# VESC_KS75600_comm.net
KiCad netlist of a schematic drawn in Altium Designer
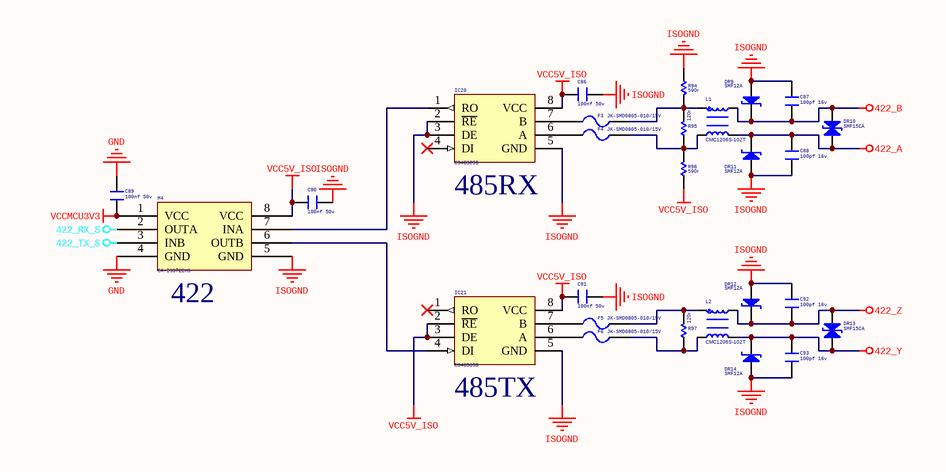
[diagram p0: VESC_KS75600_comm.SchDoc]

(export (version "E")
  (design (tool "Eeschema 10.0.6"))
  (components
    (comp (ref "C86")
      (value "100nf 50v")
      (footprint "C 0603")
      (description "无极性贴片电容")
      (fields (field (name "VOLTAGE") "50v"))
      (libsource (lib "电阻-电容-电感") (part "C"))
    )
    (comp (ref "C87")
      (value "100pf 16v")
      (footprint "C 0603")
      (description "无极性贴片电容")
      (fields (field (name "VOLTAGE") "16v"))
      (libsource (lib "电阻-电容-电感") (part "C"))
    )
    (comp (ref "C88")
      (value "100pf 16v")
      (footprint "C 0603")
      (description "无极性贴片电容")
      (fields (field (name "VOLTAGE") "16v"))
      (libsource (lib "电阻-电容-电感") (part "C"))
    )
    (comp (ref "C89")
      (value "100nf 50v")
      (footprint "C 0603")
      (description "无极性贴片电容")
      (fields (field (name "VOLTAGE") "50v"))
      (libsource (lib "电阻-电容-电感") (part "C"))
    )
    (comp (ref "C90")
      (value "100nf 50v")
      (footprint "C 0603")
      (description "无极性贴片电容")
      (fields (field (name "VOLTAGE") "50v"))
      (libsource (lib "电阻-电容-电感") (part "C"))
    )
    (comp (ref "C91")
      (value "100nf 50v")
      (footprint "C 0603")
      (description "无极性贴片电容")
      (fields (field (name "VOLTAGE") "50v"))
      (libsource (lib "电阻-电容-电感") (part "C"))
    )
    (comp (ref "C92")
      (value "100pf 16v")
      (footprint "C 0603")
      (description "无极性贴片电容")
      (fields (field (name "VOLTAGE") "16v"))
      (libsource (lib "电阻-电容-电感") (part "C"))
    )
    (comp (ref "C93")
      (value "100pf 16v")
      (footprint "C 0603")
      (description "无极性贴片电容")
      (fields (field (name "VOLTAGE") "16v"))
      (libsource (lib "电阻-电容-电感") (part "C"))
    )
    (comp (ref "DR9")
      (value "SMF12A")
      (footprint "SOD-123F")
      (description "瞬态电压抑制二极管(单向)")
      (libsource (lib "二极管-整流桥") (part "DR_S"))
    )
    (comp (ref "DR10")
      (value "SMF15CA")
      (footprint "SOD-123F")
      (description "瞬态电压抑制二极管")
      (libsource (lib "二极管-整流桥") (part "DR"))
    )
    (comp (ref "DR11")
      (value "SMF12A")
      (footprint "SOD-123F")
      (description "瞬态电压抑制二极管(单向)")
      (libsource (lib "二极管-整流桥") (part "DR_S"))
    )
    (comp (ref "DR12")
      (value "SMF12A")
      (footprint "SOD-123F")
      (description "瞬态电压抑制二极管(单向)")
      (libsource (lib "二极管-整流桥") (part "DR_S"))
    )
    (comp (ref "DR13")
      (value "SMF15CA")
      (footprint "SOD-123F")
      (description "瞬态电压抑制二极管")
      (libsource (lib "二极管-整流桥") (part "DR"))
    )
    (comp (ref "DR14")
      (value "SMF12A")
      (footprint "SOD-123F")
      (description "瞬态电压抑制二极管(单向)")
      (libsource (lib "二极管-整流桥") (part "DR_S"))
    )
    (comp (ref "F3")
      (value "JK-SMD0805-010/15V")
      (footprint "FU 0805")
      (description "贴片保险丝")
      (libsource (lib "保险丝-晶振") (part "FU"))
    )
    (comp (ref "F4")
      (value "JK-SMD0805-010/15V")
      (footprint "FU 0805")
      (description "贴片保险丝")
      (libsource (lib "保险丝-晶振") (part "FU"))
    )
    (comp (ref "F5")
      (value "JK-SMD0805-010/15V")
      (footprint "FU 0805")
      (description "贴片保险丝")
      (libsource (lib "保险丝-晶振") (part "FU"))
    )
    (comp (ref "F6")
      (value "JK-SMD0805-010/15V")
      (footprint "FU 0805")
      (description "贴片保险丝")
      (libsource (lib "保险丝-晶振") (part "FU"))
    )
    (comp (ref "IC20")
      (value "CS48505S")
      (footprint "SOP8_N")
      (description "RS485总线收发芯片")
      (libsource (lib "IC芯片") (part "SP3485"))
    )
    (comp (ref "IC21")
      (value "CS48505S")
      (footprint "SOP8_N")
      (description "RS485总线收发芯片")
      (libsource (lib "IC芯片") (part "SP3485"))
    )
    (comp (ref "L1")
      (value "CMC1206S-102T")
      (footprint "D_C_C_1206")
      (description "共模电感")
      (libsource (lib "电阻-电容-电感") (part "L-CMC"))
    )
    (comp (ref "L2")
      (value "CMC1206S-102T")
      (footprint "D_C_C_1206")
      (description "共模电感")
      (libsource (lib "电阻-电容-电感") (part "L-CMC"))
    )
    (comp (ref "M4")
      (value "CA-IS3722HS")
      (footprint "SOP8_N")
      (description "正反向数字隔离器")
      (libsource (lib "IC芯片") (part "CA-IS3722"))
    )
    (comp (ref "R94")
      (value "590r")
      (footprint "R 0603")
      (description "贴片电阻")
      (libsource (lib "电阻-电容-电感") (part "R"))
    )
    (comp (ref "R95")
      (value "120r")
      (footprint "R 0603")
      (description "贴片电阻")
      (libsource (lib "电阻-电容-电感") (part "R"))
    )
    (comp (ref "R96")
      (value "590r")
      (footprint "R 0603")
      (description "贴片电阻")
      (libsource (lib "电阻-电容-电感") (part "R"))
    )
    (comp (ref "R97")
      (value "120r")
      (footprint "R 0603")
      (description "贴片电阻")
      (libsource (lib "电阻-电容-电感") (part "R"))
    )
  )
  (nets
    (net (code "1") (name "422_A") (class "Default")
      (node (ref "C88") (pin "2") (pinfunction "2_2") (pintype "passive"))
      (node (ref "DR10") (pin "2") (pinfunction "K_2") (pintype "passive"))
      (node (ref "DR11") (pin "2") (pinfunction "K_2") (pintype "passive"))
      (node (ref "L1") (pin "3") (pinfunction "3_3") (pintype "passive"))
    )
    (net (code "2") (name "422_B") (class "Default")
      (node (ref "C87") (pin "2") (pinfunction "2_2") (pintype "passive"))
      (node (ref "DR10") (pin "1") (pinfunction "A_1") (pintype "passive"))
      (node (ref "DR9") (pin "2") (pinfunction "K_2") (pintype "passive"))
      (node (ref "L1") (pin "2") (pinfunction "2_2") (pintype "passive"))
    )
    (net (code "3") (name "422_RX_S") (class "Default")
      (node (ref "M4") (pin "2") (pinfunction "OUTA_2") (pintype "passive"))
    )
    (net (code "4") (name "422_TX_S") (class "Default")
      (node (ref "M4") (pin "3") (pinfunction "INB_3") (pintype "passive"))
    )
    (net (code "5") (name "422_Y") (class "Default")
      (node (ref "C93") (pin "2") (pinfunction "2_2") (pintype "passive"))
      (node (ref "DR13") (pin "2") (pinfunction "K_2") (pintype "passive"))
      (node (ref "DR14") (pin "2") (pinfunction "K_2") (pintype "passive"))
      (node (ref "L2") (pin "3") (pinfunction "3_3") (pintype "passive"))
    )
    (net (code "6") (name "422_Z") (class "Default")
      (node (ref "C92") (pin "2") (pinfunction "2_2") (pintype "passive"))
      (node (ref "DR12") (pin "2") (pinfunction "K_2") (pintype "passive"))
      (node (ref "DR13") (pin "1") (pinfunction "A_1") (pintype "passive"))
      (node (ref "L2") (pin "2") (pinfunction "2_2") (pintype "passive"))
    )
    (net (code "7") (name "GND") (class "Default")
      (node (ref "C89") (pin "1") (pinfunction "1_1") (pintype "passive"))
      (node (ref "M4") (pin "4") (pinfunction "GND_4") (pintype "passive"))
    )
    (net (code "8") (name "ISOGND") (class "Default")
      (node (ref "C86") (pin "2") (pinfunction "2_2") (pintype "passive"))
      (node (ref "C87") (pin "1") (pinfunction "1_1") (pintype "passive"))
      (node (ref "C88") (pin "1") (pinfunction "1_1") (pintype "passive"))
      (node (ref "C90") (pin "2") (pinfunction "2_2") (pintype "passive"))
      (node (ref "C91") (pin "2") (pinfunction "2_2") (pintype "passive"))
      (node (ref "C92") (pin "1") (pinfunction "1_1") (pintype "passive"))
      (node (ref "C93") (pin "1") (pinfunction "1_1") (pintype "passive"))
      (node (ref "DR11") (pin "1") (pinfunction "A_1") (pintype "passive"))
      (node (ref "DR12") (pin "1") (pinfunction "A_1") (pintype "passive"))
      (node (ref "DR14") (pin "1") (pinfunction "A_1") (pintype "passive"))
      (node (ref "DR9") (pin "1") (pinfunction "A_1") (pintype "passive"))
      (node (ref "IC20") (pin "2") (pinfunction "~{RE}_2") (pintype "passive"))
      (node (ref "IC20") (pin "3") (pinfunction "DE_3") (pintype "passive"))
      (node (ref "IC20") (pin "5") (pinfunction "GND_5") (pintype "passive"))
      (node (ref "IC21") (pin "5") (pinfunction "GND_5") (pintype "passive"))
      (node (ref "M4") (pin "5") (pinfunction "GND_5") (pintype "passive"))
      (node (ref "R94") (pin "1") (pinfunction "1_1") (pintype "passive"))
    )
    (net (code "9") (name "Net-(F3-Pad2)") (class "Default")
      (node (ref "F3") (pin "2") (pinfunction "2_2") (pintype "passive"))
      (node (ref "L1") (pin "1") (pinfunction "1_1") (pintype "passive"))
      (node (ref "R94") (pin "2") (pinfunction "2_2") (pintype "passive"))
      (node (ref "R95") (pin "2") (pinfunction "2_2") (pintype "passive"))
    )
    (net (code "10") (name "Net-(F4-Pad2)") (class "Default")
      (node (ref "F4") (pin "2") (pinfunction "2_2") (pintype "passive"))
      (node (ref "L1") (pin "4") (pinfunction "4_4") (pintype "passive"))
      (node (ref "R95") (pin "1") (pinfunction "1_1") (pintype "passive"))
      (node (ref "R96") (pin "2") (pinfunction "2_2") (pintype "passive"))
    )
    (net (code "11") (name "Net-(F5-Pad2)") (class "Default")
      (node (ref "F5") (pin "2") (pinfunction "2_2") (pintype "passive"))
      (node (ref "L2") (pin "1") (pinfunction "1_1") (pintype "passive"))
      (node (ref "R97") (pin "2") (pinfunction "2_2") (pintype "passive"))
    )
    (net (code "12") (name "Net-(F6-Pad2)") (class "Default")
      (node (ref "F6") (pin "2") (pinfunction "2_2") (pintype "passive"))
      (node (ref "L2") (pin "4") (pinfunction "4_4") (pintype "passive"))
      (node (ref "R97") (pin "1") (pinfunction "1_1") (pintype "passive"))
    )
    (net (code "13") (name "Net-(IC20-A)") (class "Default")
      (node (ref "F4") (pin "1") (pinfunction "1_1") (pintype "passive"))
      (node (ref "IC20") (pin "6") (pinfunction "A_6") (pintype "passive"))
    )
    (net (code "14") (name "Net-(IC20-B)") (class "Default")
      (node (ref "F3") (pin "1") (pinfunction "1_1") (pintype "passive"))
      (node (ref "IC20") (pin "7") (pinfunction "B_7") (pintype "passive"))
    )
    (net (code "15") (name "Net-(IC20-RO)") (class "Default")
      (node (ref "IC20") (pin "1") (pinfunction "RO_1") (pintype "output"))
      (node (ref "M4") (pin "7") (pinfunction "INA_7") (pintype "passive"))
    )
    (net (code "16") (name "Net-(IC21-A)") (class "Default")
      (node (ref "F6") (pin "1") (pinfunction "1_1") (pintype "passive"))
      (node (ref "IC21") (pin "6") (pinfunction "A_6") (pintype "passive"))
    )
    (net (code "17") (name "Net-(IC21-B)") (class "Default")
      (node (ref "F5") (pin "1") (pinfunction "1_1") (pintype "passive"))
      (node (ref "IC21") (pin "7") (pinfunction "B_7") (pintype "passive"))
    )
    (net (code "18") (name "Net-(IC21-DI)") (class "Default")
      (node (ref "IC21") (pin "4") (pinfunction "DI_4") (pintype "input"))
      (node (ref "M4") (pin "6") (pinfunction "OUTB_6") (pintype "passive"))
    )
    (net (code "19") (name "VCC5V_ISO") (class "Default")
      (node (ref "C86") (pin "1") (pinfunction "1_1") (pintype "passive"))
      (node (ref "C90") (pin "1") (pinfunction "1_1") (pintype "passive"))
      (node (ref "C91") (pin "1") (pinfunction "1_1") (pintype "passive"))
      (node (ref "IC20") (pin "8") (pinfunction "VCC_8") (pintype "passive"))
      (node (ref "IC21") (pin "2") (pinfunction "~{RE}_2") (pintype "passive"))
      (node (ref "IC21") (pin "3") (pinfunction "DE_3") (pintype "passive"))
      (node (ref "IC21") (pin "8") (pinfunction "VCC_8") (pintype "passive"))
      (node (ref "M4") (pin "8") (pinfunction "VCC_8") (pintype "passive"))
      (node (ref "R96") (pin "1") (pinfunction "1_1") (pintype "passive"))
    )
    (net (code "20") (name "VCCMCU3V3") (class "Default")
      (node (ref "C89") (pin "2") (pinfunction "2_2") (pintype "passive"))
      (node (ref "M4") (pin "1") (pinfunction "VCC_1") (pintype "passive"))
    )
    (net (code "21") (name "unconnected-(IC20-DI-Pad4)") (class "Default")
      (node (ref "IC20") (pin "4") (pinfunction "DI_4") (pintype "input+no_connect"))
    )
    (net (code "22") (name "unconnected-(IC21-RO-Pad1)") (class "Default")
      (node (ref "IC21") (pin "1") (pinfunction "RO_1") (pintype "output+no_connect"))
    )
  )
)
